# Breakout.net
KiCad netlist of a schematic drawn in EAGLE
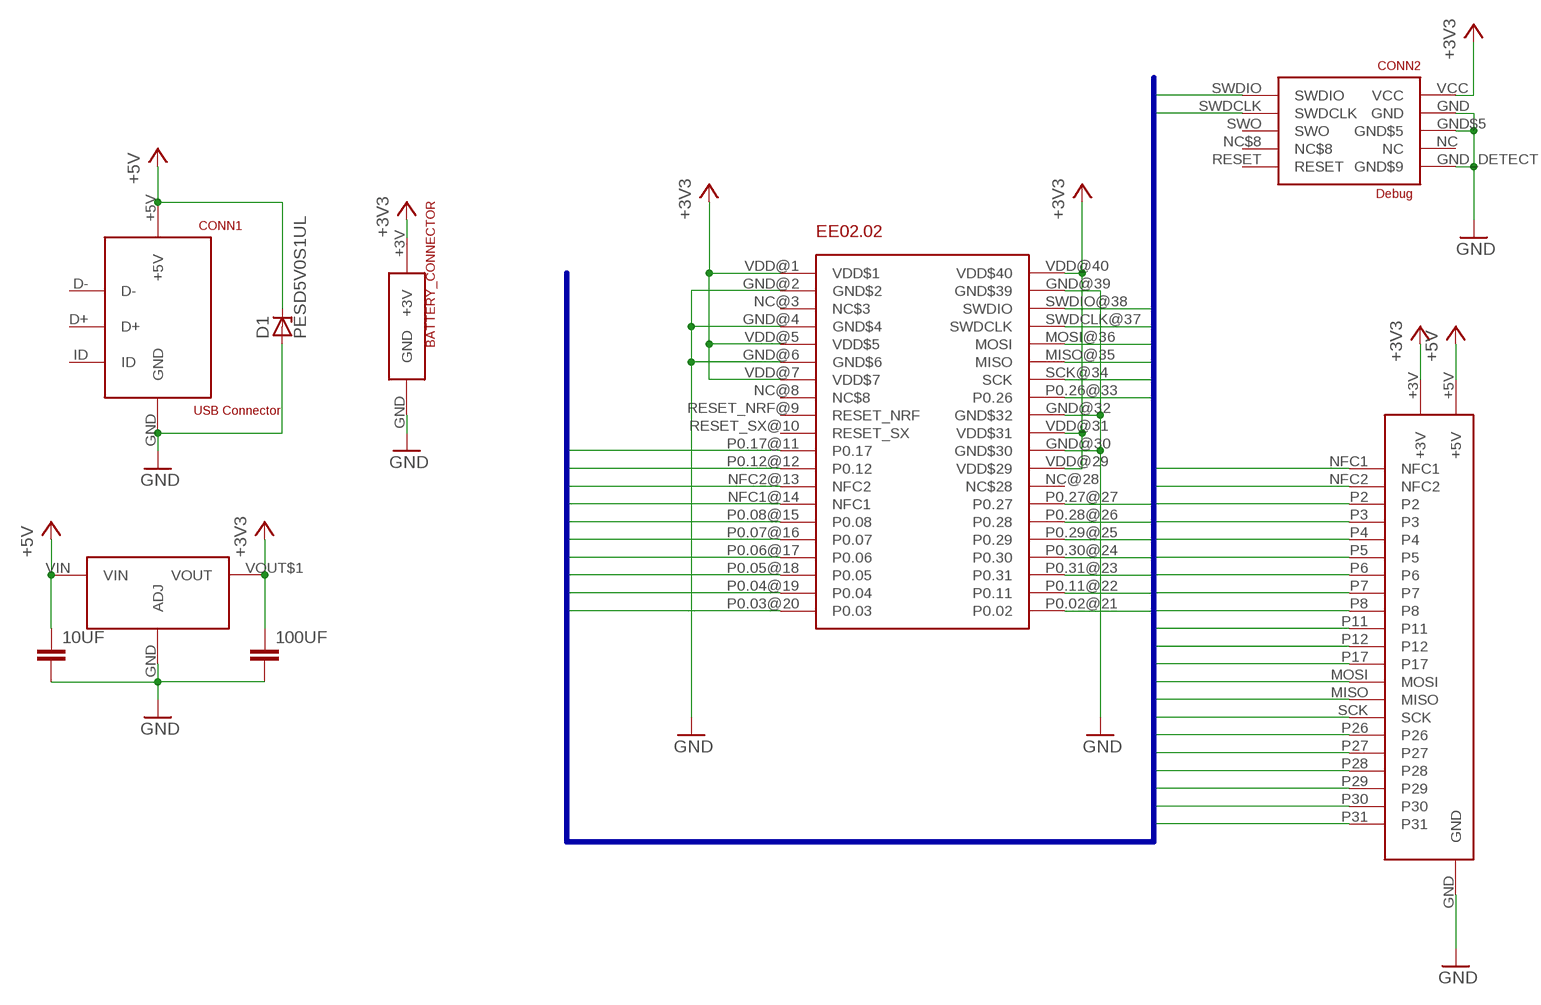
[diagram p0: schematic, sheet 1]

(export (version "E")
  (design (tool "Eeschema 10.0.6"))
  (components
    (comp (ref "10UF")
      (value "4.7UF-0805")
      (footprint "eagle-import:0805")
      (libsource (lib "eagle-import") (part "4.7UF-0805"))
    )
    (comp (ref "100UF")
      (value "4.7UF-0805")
      (footprint "eagle-import:0805")
      (libsource (lib "eagle-import") (part "4.7UF-0805"))
    )
    (comp (ref "BATTERY_CONNECTOR")
      (value "3V_BATTERY_CONNECTOR")
      (footprint "eagle-import:3V_BATTERY_CONNECTOR")
      (libsource (lib "eagle-import") (part "3V_BATTERY_CONNECTOR"))
    )
    (comp (ref "CONN1")
      (value "USB Connector")
      (footprint "eagle-import:USB_MICRO_B")
      (libsource (lib "eagle-import") (part "USB_MICRO_B"))
    )
    (comp (ref "CONN2")
      (value "Debug")
      (footprint "eagle-import:NRF52-P19-CONNECTOR")
      (libsource (lib "eagle-import") (part "DEBUGHEADER"))
    )
    (comp (ref "D1")
      (value "PESD5V0S1UL")
      (footprint "eagle-import:SOD882")
      (libsource (lib "eagle-import") (part "PESD5V0S1UL"))
    )
    (comp (ref "EE02.02")
      (value "EE02_02")
      (footprint "eagle-import:EE02_02")
      (libsource (lib "eagle-import") (part "EE02_02"))
    )
    (comp (ref "U$4")
      (value "LM1117")
      (footprint "eagle-import:SOT-223")
      (libsource (lib "eagle-import") (part "LM1117"))
    )
    (comp (ref "U$5")
      (value "EE02_SHIELD_HEADERSHIELD")
      (footprint "eagle-import:EE02_SHIELD_HEADER")
      (libsource (lib "eagle-import") (part "EE02_SHIELD_HEADERSHIELD"))
    )
  )
  (nets
    (net (code "1") (name "+3V3") (class "Default")
      (node (ref "100UF") (pin "1") (pinfunction "1_1") (pintype "passive"))
      (node (ref "BATTERY_CONNECTOR") (pin "+3V") (pinfunction "+3V_+3V") (pintype "bidirectional"))
      (node (ref "CONN2") (pin "VCC") (pinfunction "VCC_VCC") (pintype "bidirectional"))
      (node (ref "EE02.02") (pin "VDD@1") (pinfunction "VDD$1_VDD@1") (pintype "bidirectional"))
      (node (ref "EE02.02") (pin "VDD@29") (pinfunction "VDD$29_VDD@29") (pintype "bidirectional"))
      (node (ref "EE02.02") (pin "VDD@31") (pinfunction "VDD$31_VDD@31") (pintype "bidirectional"))
      (node (ref "EE02.02") (pin "VDD@40") (pinfunction "VDD$40_VDD@40") (pintype "bidirectional"))
      (node (ref "EE02.02") (pin "VDD@5") (pinfunction "VDD$5_VDD@5") (pintype "bidirectional"))
      (node (ref "EE02.02") (pin "VDD@7") (pinfunction "VDD$7_VDD@7") (pintype "bidirectional"))
      (node (ref "U$4") (pin "VOUT$1") (pinfunction "VOUT_VOUT$1") (pintype "bidirectional"))
      (node (ref "U$5") (pin "+3V") (pinfunction "+3V_+3V") (pintype "bidirectional"))
    )
    (net (code "2") (name "+5V") (class "Default")
      (node (ref "10UF") (pin "1") (pinfunction "1_1") (pintype "passive"))
      (node (ref "CONN1") (pin "+5V") (pinfunction "+5V_+5V") (pintype "bidirectional"))
      (node (ref "D1") (pin "CATHODE") (pinfunction "C_CATHODE") (pintype "passive"))
      (node (ref "U$4") (pin "VIN") (pinfunction "VIN_VIN") (pintype "bidirectional"))
      (node (ref "U$5") (pin "+5V") (pinfunction "+5V_+5V") (pintype "bidirectional"))
    )
    (net (code "3") (name "/MISO") (class "Default")
      (node (ref "EE02.02") (pin "MISO@35") (pinfunction "MISO_MISO@35") (pintype "bidirectional"))
      (node (ref "U$5") (pin "MISO") (pinfunction "MISO_MISO") (pintype "bidirectional"))
    )
    (net (code "4") (name "/MOSI") (class "Default")
      (node (ref "EE02.02") (pin "MOSI@36") (pinfunction "MOSI_MOSI@36") (pintype "bidirectional"))
      (node (ref "U$5") (pin "MOSI") (pinfunction "MOSI_MOSI") (pintype "bidirectional"))
    )
    (net (code "5") (name "/NFC1") (class "Default")
      (node (ref "EE02.02") (pin "NFC1@14") (pinfunction "NFC1_NFC1@14") (pintype "bidirectional"))
      (node (ref "U$5") (pin "NFC1") (pinfunction "NFC1_NFC1") (pintype "bidirectional"))
    )
    (net (code "6") (name "/NFC2") (class "Default")
      (node (ref "EE02.02") (pin "NFC2@13") (pinfunction "NFC2_NFC2@13") (pintype "bidirectional"))
      (node (ref "U$5") (pin "NFC2") (pinfunction "NFC2_NFC2") (pintype "bidirectional"))
    )
    (net (code "7") (name "/P2") (class "Default")
      (node (ref "EE02.02") (pin "P0.02@21") (pinfunction "P0.02_P0.02@21") (pintype "bidirectional"))
      (node (ref "U$5") (pin "P2") (pinfunction "P2_P2") (pintype "bidirectional"))
    )
    (net (code "8") (name "/P3") (class "Default")
      (node (ref "EE02.02") (pin "P0.03@20") (pinfunction "P0.03_P0.03@20") (pintype "bidirectional"))
      (node (ref "U$5") (pin "P3") (pinfunction "P3_P3") (pintype "bidirectional"))
    )
    (net (code "9") (name "/P4") (class "Default")
      (node (ref "EE02.02") (pin "P0.04@19") (pinfunction "P0.04_P0.04@19") (pintype "bidirectional"))
      (node (ref "U$5") (pin "P4") (pinfunction "P4_P4") (pintype "bidirectional"))
    )
    (net (code "10") (name "/P5") (class "Default")
      (node (ref "EE02.02") (pin "P0.05@18") (pinfunction "P0.05_P0.05@18") (pintype "bidirectional"))
      (node (ref "U$5") (pin "P5") (pinfunction "P5_P5") (pintype "bidirectional"))
    )
    (net (code "11") (name "/P6") (class "Default")
      (node (ref "EE02.02") (pin "P0.06@17") (pinfunction "P0.06_P0.06@17") (pintype "bidirectional"))
      (node (ref "U$5") (pin "P6") (pinfunction "P6_P6") (pintype "bidirectional"))
    )
    (net (code "12") (name "/P7") (class "Default")
      (node (ref "EE02.02") (pin "P0.07@16") (pinfunction "P0.07_P0.07@16") (pintype "bidirectional"))
      (node (ref "U$5") (pin "P7") (pinfunction "P7_P7") (pintype "bidirectional"))
    )
    (net (code "13") (name "/P8") (class "Default")
      (node (ref "EE02.02") (pin "P0.08@15") (pinfunction "P0.08_P0.08@15") (pintype "bidirectional"))
      (node (ref "U$5") (pin "P8") (pinfunction "P8_P8") (pintype "bidirectional"))
    )
    (net (code "14") (name "/P11") (class "Default")
      (node (ref "EE02.02") (pin "P0.11@22") (pinfunction "P0.11_P0.11@22") (pintype "bidirectional"))
      (node (ref "U$5") (pin "P11") (pinfunction "P11_P11") (pintype "bidirectional"))
    )
    (net (code "15") (name "/P12") (class "Default")
      (node (ref "EE02.02") (pin "P0.12@12") (pinfunction "P0.12_P0.12@12") (pintype "bidirectional"))
      (node (ref "U$5") (pin "P12") (pinfunction "P12_P12") (pintype "bidirectional"))
    )
    (net (code "16") (name "/P17") (class "Default")
      (node (ref "EE02.02") (pin "P0.17@11") (pinfunction "P0.17_P0.17@11") (pintype "bidirectional"))
      (node (ref "U$5") (pin "P17") (pinfunction "P17_P17") (pintype "bidirectional"))
    )
    (net (code "17") (name "/P26") (class "Default")
      (node (ref "EE02.02") (pin "P0.26@33") (pinfunction "P0.26_P0.26@33") (pintype "bidirectional"))
      (node (ref "U$5") (pin "P26") (pinfunction "P26_P26") (pintype "bidirectional"))
    )
    (net (code "18") (name "/P27") (class "Default")
      (node (ref "EE02.02") (pin "P0.27@27") (pinfunction "P0.27_P0.27@27") (pintype "bidirectional"))
      (node (ref "U$5") (pin "P27") (pinfunction "P27_P27") (pintype "bidirectional"))
    )
    (net (code "19") (name "/P28") (class "Default")
      (node (ref "EE02.02") (pin "P0.28@26") (pinfunction "P0.28_P0.28@26") (pintype "bidirectional"))
      (node (ref "U$5") (pin "P28") (pinfunction "P28_P28") (pintype "bidirectional"))
    )
    (net (code "20") (name "/P29") (class "Default")
      (node (ref "EE02.02") (pin "P0.29@25") (pinfunction "P0.29_P0.29@25") (pintype "bidirectional"))
      (node (ref "U$5") (pin "P29") (pinfunction "P29_P29") (pintype "bidirectional"))
    )
    (net (code "21") (name "/P30") (class "Default")
      (node (ref "EE02.02") (pin "P0.30@24") (pinfunction "P0.30_P0.30@24") (pintype "bidirectional"))
      (node (ref "U$5") (pin "P30") (pinfunction "P30_P30") (pintype "bidirectional"))
    )
    (net (code "22") (name "/P31") (class "Default")
      (node (ref "EE02.02") (pin "P0.31@23") (pinfunction "P0.31_P0.31@23") (pintype "bidirectional"))
      (node (ref "U$5") (pin "P31") (pinfunction "P31_P31") (pintype "bidirectional"))
    )
    (net (code "23") (name "/SCK") (class "Default")
      (node (ref "EE02.02") (pin "SCK@34") (pinfunction "SCK_SCK@34") (pintype "bidirectional"))
      (node (ref "U$5") (pin "SCK") (pinfunction "SCK_SCK") (pintype "bidirectional"))
    )
    (net (code "24") (name "/SWDCLK") (class "Default")
      (node (ref "CONN2") (pin "SWDCLK") (pinfunction "SWDCLK_SWDCLK") (pintype "bidirectional"))
      (node (ref "EE02.02") (pin "SWDCLK@37") (pinfunction "SWDCLK_SWDCLK@37") (pintype "bidirectional"))
    )
    (net (code "25") (name "/SWDIO") (class "Default")
      (node (ref "CONN2") (pin "SWDIO") (pinfunction "SWDIO_SWDIO") (pintype "bidirectional"))
      (node (ref "EE02.02") (pin "SWDIO@38") (pinfunction "SWDIO_SWDIO@38") (pintype "bidirectional"))
    )
    (net (code "26") (name "GND") (class "Default")
      (node (ref "100UF") (pin "2") (pinfunction "2_2") (pintype "passive"))
      (node (ref "10UF") (pin "2") (pinfunction "2_2") (pintype "passive"))
      (node (ref "BATTERY_CONNECTOR") (pin "GND") (pinfunction "GND_GND") (pintype "bidirectional"))
      (node (ref "CONN1") (pin "GND") (pinfunction "GND_GND") (pintype "bidirectional"))
      (node (ref "CONN2") (pin "GND") (pinfunction "GND_GND") (pintype "bidirectional"))
      (node (ref "CONN2") (pin "GND$5") (pinfunction "GND$5_GND$5") (pintype "bidirectional"))
      (node (ref "CONN2") (pin "GND_DETECT") (pinfunction "GND$9_GND_DETECT") (pintype "bidirectional"))
      (node (ref "D1") (pin "ANODE") (pinfunction "A_ANODE") (pintype "passive"))
      (node (ref "EE02.02") (pin "GND@2") (pinfunction "GND$2_GND@2") (pintype "bidirectional"))
      (node (ref "EE02.02") (pin "GND@30") (pinfunction "GND$30_GND@30") (pintype "bidirectional"))
      (node (ref "EE02.02") (pin "GND@32") (pinfunction "GND$32_GND@32") (pintype "bidirectional"))
      (node (ref "EE02.02") (pin "GND@39") (pinfunction "GND$39_GND@39") (pintype "bidirectional"))
      (node (ref "EE02.02") (pin "GND@4") (pinfunction "GND$4_GND@4") (pintype "bidirectional"))
      (node (ref "EE02.02") (pin "GND@6") (pinfunction "GND$6_GND@6") (pintype "bidirectional"))
      (node (ref "U$4") (pin "GND") (pinfunction "ADJ_GND") (pintype "bidirectional"))
      (node (ref "U$5") (pin "GND") (pinfunction "GND_GND") (pintype "bidirectional"))
    )
    (net (code "27") (name "unconnected-(CONN1-PadD+)") (class "Default")
      (node (ref "CONN1") (pin "D+") (pinfunction "D+_D+") (pintype "bidirectional"))
    )
    (net (code "28") (name "unconnected-(CONN1-PadD-)") (class "Default")
      (node (ref "CONN1") (pin "D-") (pinfunction "D-_D-") (pintype "bidirectional"))
    )
    (net (code "29") (name "unconnected-(CONN1-PadID)") (class "Default")
      (node (ref "CONN1") (pin "ID") (pinfunction "ID_ID") (pintype "bidirectional"))
    )
    (net (code "30") (name "unconnected-(CONN2-PadNC$8)") (class "Default")
      (node (ref "CONN2") (pin "NC$8") (pinfunction "NC$8_NC$8") (pintype "bidirectional"))
    )
    (net (code "31") (name "unconnected-(CONN2-PadNC)") (class "Default")
      (node (ref "CONN2") (pin "NC") (pinfunction "NC_NC") (pintype "bidirectional"))
    )
    (net (code "32") (name "unconnected-(CONN2-PadRESET)") (class "Default")
      (node (ref "CONN2") (pin "RESET") (pinfunction "RESET_RESET") (pintype "bidirectional"))
    )
    (net (code "33") (name "unconnected-(CONN2-PadSWO)") (class "Default")
      (node (ref "CONN2") (pin "SWO") (pinfunction "SWO_SWO") (pintype "bidirectional"))
    )
    (net (code "34") (name "unconnected-(EE02.02-NC$3-PadNC@3)") (class "Default")
      (node (ref "EE02.02") (pin "NC@3") (pinfunction "NC$3_NC@3") (pintype "bidirectional"))
    )
    (net (code "35") (name "unconnected-(EE02.02-NC$8-PadNC@8)") (class "Default")
      (node (ref "EE02.02") (pin "NC@8") (pinfunction "NC$8_NC@8") (pintype "bidirectional"))
    )
    (net (code "36") (name "unconnected-(EE02.02-NC$28-PadNC@28)") (class "Default")
      (node (ref "EE02.02") (pin "NC@28") (pinfunction "NC$28_NC@28") (pintype "bidirectional"))
    )
    (net (code "37") (name "unconnected-(EE02.02-RESET_NRF-PadRESET_NRF@9)") (class "Default")
      (node (ref "EE02.02") (pin "RESET_NRF@9") (pinfunction "RESET_NRF_RESET_NRF@9") (pintype "bidirectional"))
    )
    (net (code "38") (name "unconnected-(EE02.02-RESET_SX-PadRESET_SX@10)") (class "Default")
      (node (ref "EE02.02") (pin "RESET_SX@10") (pinfunction "RESET_SX_RESET_SX@10") (pintype "bidirectional"))
    )
  )
)
